# can.net
KiCad netlist of a schematic drawn in Altium Designer
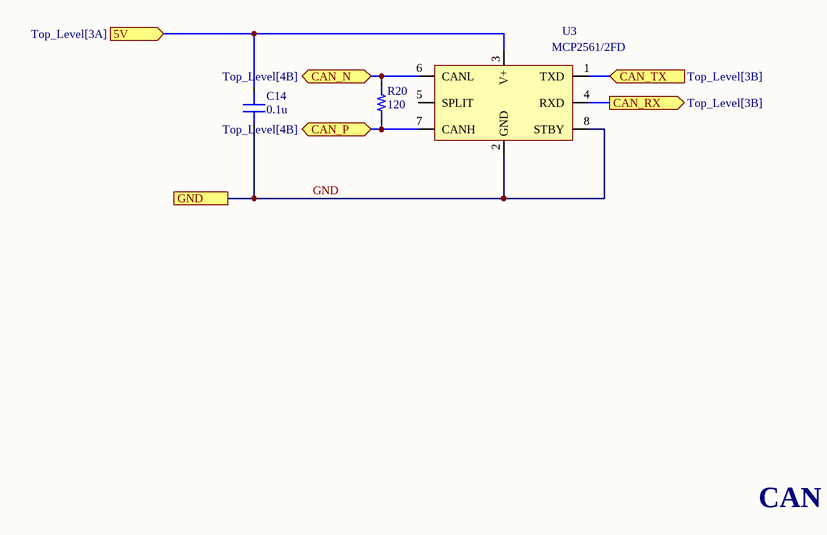
[diagram p0: can.SchDoc]

(export (version "E")
  (design (tool "Eeschema 10.0.6"))
  (components
    (comp (ref "C14")
      (value "0.1u")
      (footprint "0603_CAP")
      (fields (field (name "Comment") "Capacitor"))
      (libsource (lib "Capacitors") (part "Capacitor"))
    )
    (comp (ref "R20")
      (value "120")
      (footprint "0603_RES")
      (fields (field (name "Comment") "Resistor"))
      (libsource (lib "Resistors") (part "Resistor"))
    )
    (comp (ref "U3")
      (value "MCP2561/2FD")
      (footprint "SOIC-8")
      (description "1/1 Transceiver CANbus")
      (libsource (lib "Interfaces") (part "MCP2561/2FD"))
    )
  )
  (nets
    (net (code "1") (name "/5V") (class "Default")
      (node (ref "C14") (pin "1") (pinfunction "1_1") (pintype "passive"))
      (node (ref "U3") (pin "3") (pinfunction "V+_3") (pintype "passive"))
    )
    (net (code "2") (name "/CAN_N") (class "Default")
      (node (ref "R20") (pin "2") (pinfunction "2_2") (pintype "passive"))
      (node (ref "U3") (pin "6") (pinfunction "CANL_6") (pintype "passive"))
    )
    (net (code "3") (name "/CAN_P") (class "Default")
      (node (ref "R20") (pin "1") (pinfunction "1_1") (pintype "passive"))
      (node (ref "U3") (pin "7") (pinfunction "CANH_7") (pintype "passive"))
    )
    (net (code "4") (name "/CAN_RX") (class "Default")
      (node (ref "U3") (pin "4") (pinfunction "RXD_4") (pintype "passive"))
    )
    (net (code "5") (name "/CAN_TX") (class "Default")
      (node (ref "U3") (pin "1") (pinfunction "TXD_1") (pintype "passive"))
    )
    (net (code "6") (name "/GND") (class "Default")
      (node (ref "C14") (pin "2") (pinfunction "2_2") (pintype "passive"))
      (node (ref "U3") (pin "2") (pinfunction "GND_2") (pintype "passive"))
      (node (ref "U3") (pin "8") (pinfunction "STBY_8") (pintype "passive"))
    )
    (net (code "7") (name "unconnected-(U3-SPLIT-Pad5)") (class "Default")
      (node (ref "U3") (pin "5") (pinfunction "SPLIT_5") (pintype "passive"))
    )
  )
)
